# SDcard_eMMC.net
KiCad netlist of a schematic drawn in Altium Designer
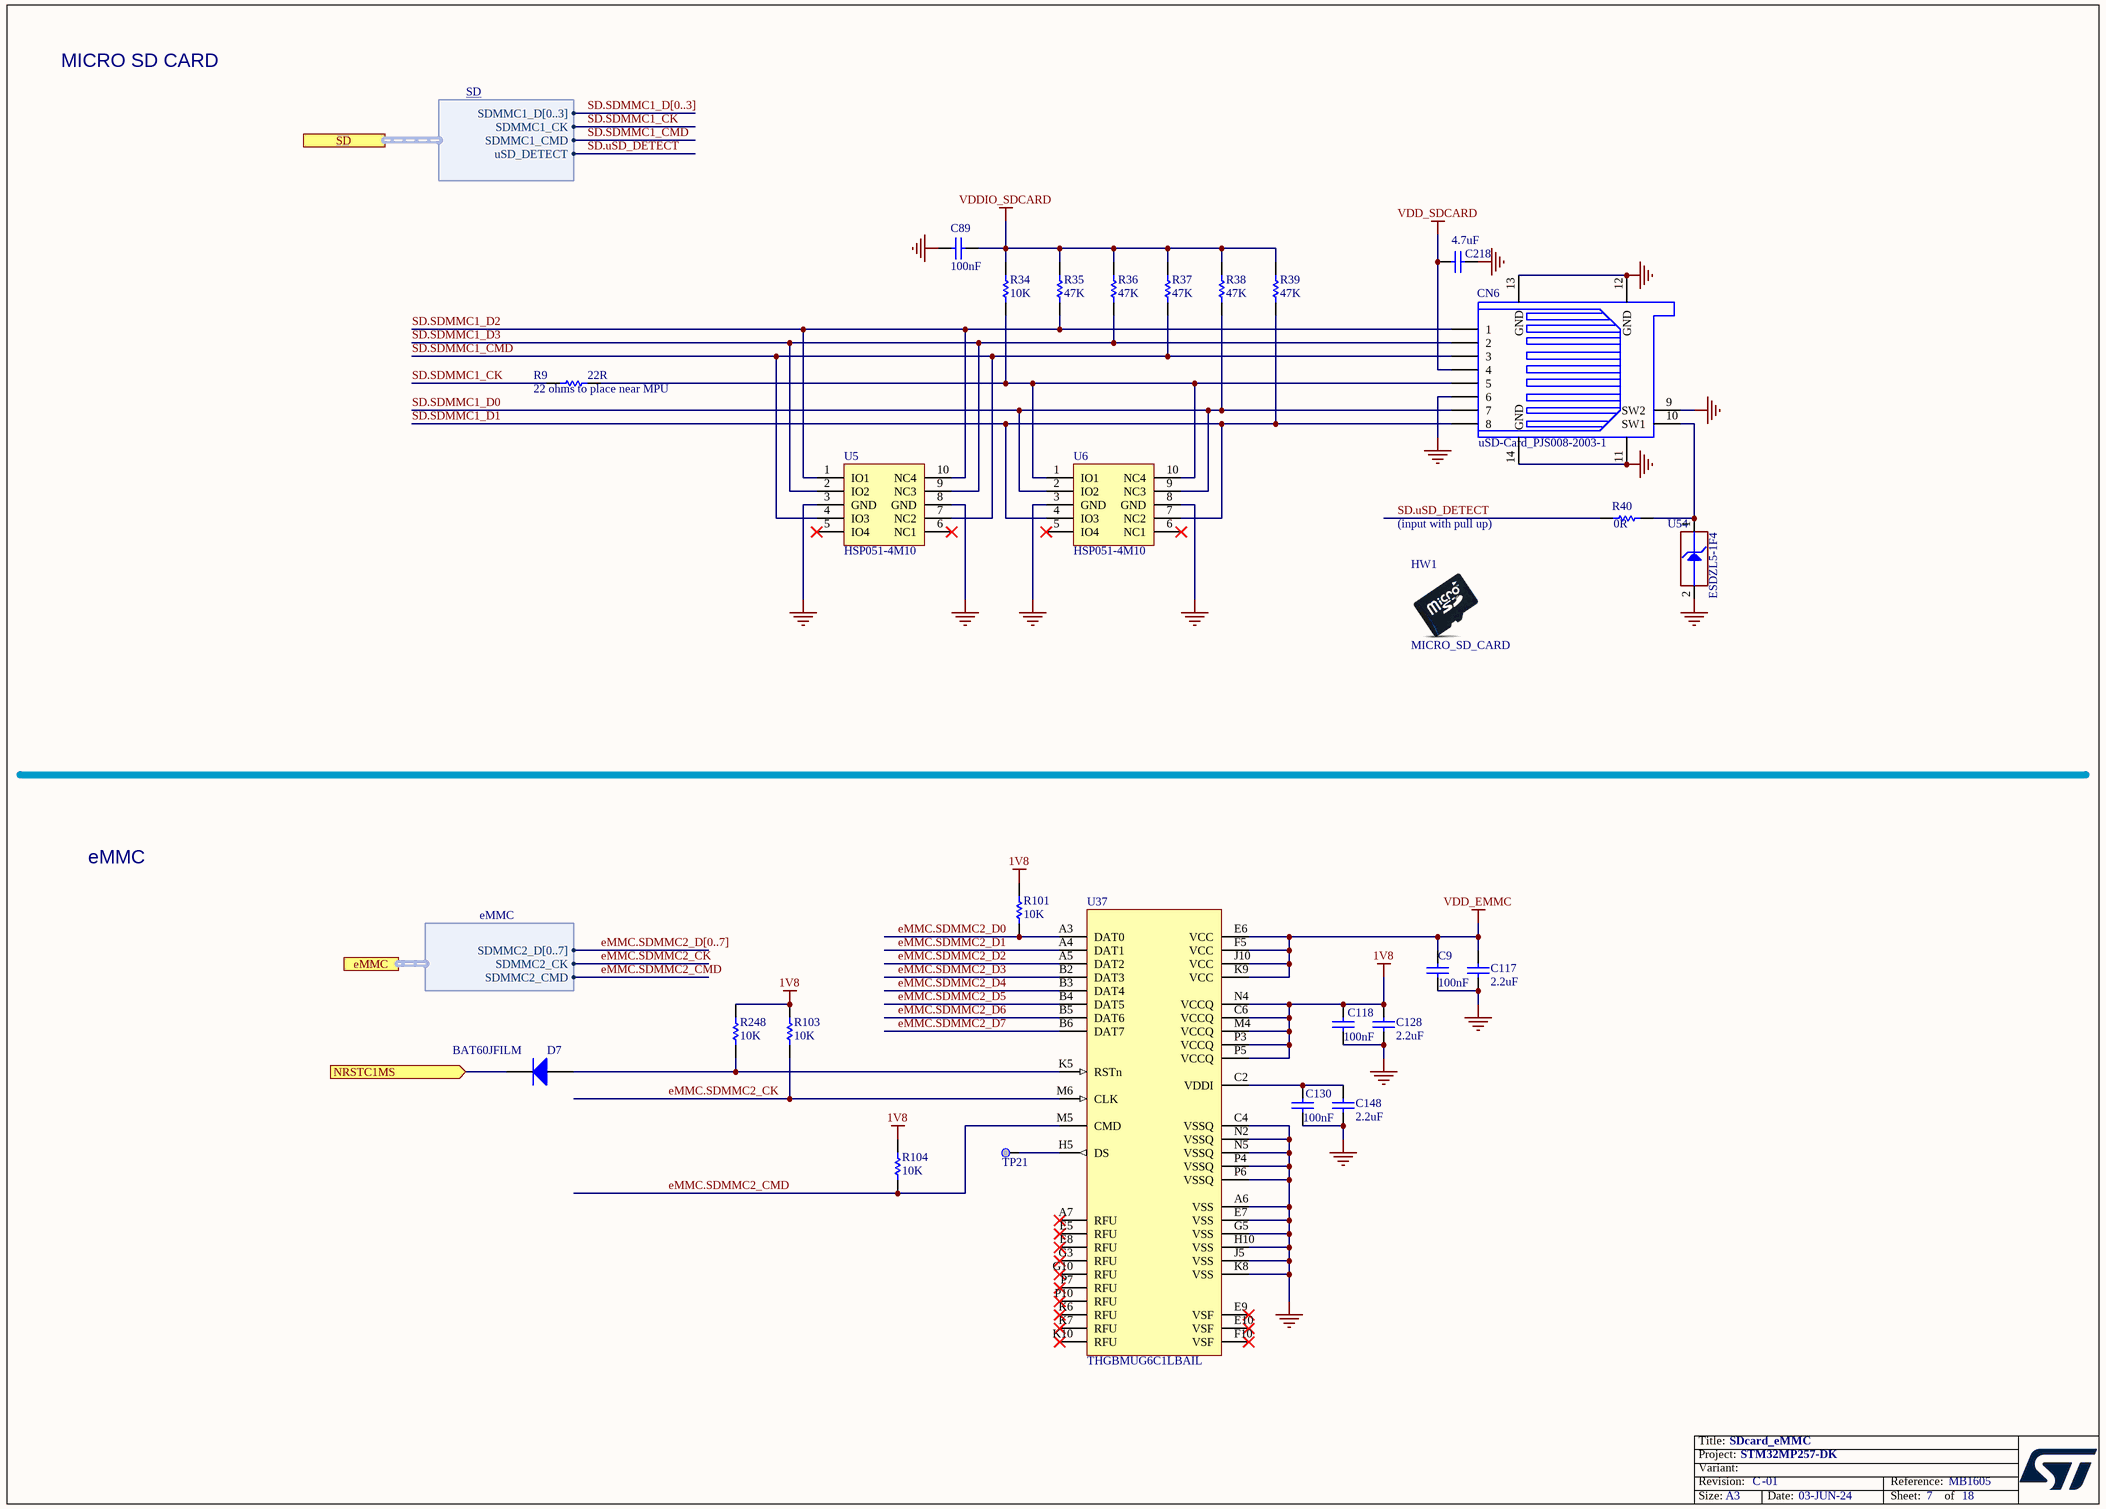
[diagram p0: SDcard_eMMC.SchDoc]

(export (version "E")
  (design (tool "Eeschema 10.0.6"))
  (components
    (comp (ref "C9")
      (value "100nF")
      (footprint "C0402")
      (description "Capacitor, MLCC, 100nF, 16V, X7R, +/-10%, 0402, T=0.5mm")
      (fields (field (name "INTERNAL_PART_NUMBER") "MCD-00006") (field (name "MANUFACTURER") "YAGEO"))
      (libsource (lib "MCD_PARTS_database") (part "Capacitor"))
    )
    (comp (ref "C89")
      (value "100nF")
      (footprint "C0402")
      (description "Capacitor, MLCC, 100nF, 16V, X7R, +/-10%, 0402, T=0.5mm")
      (fields (field (name "INTERNAL_PART_NUMBER") "MCD-00006") (field (name "MANUFACTURER") "YAGEO"))
      (libsource (lib "MCD_PARTS_database") (part "Capacitor"))
    )
    (comp (ref "C117")
      (value "2.2uF")
      (footprint "C0402")
      (description "Capacitor, MLCC, 2.2uF, 6.3V, X5R, +/-10%, 0402, T=0.5mm")
      (fields (field (name "INTERNAL_PART_NUMBER") "MCD-02606") (field (name "MANUFACTURER") "YAGEO"))
      (libsource (lib "MCD_PARTS_database") (part "Capacitor"))
    )
    (comp (ref "C118")
      (value "100nF")
      (footprint "C0402")
      (description "Capacitor, MLCC, 100nF, 16V, X7R, +/-10%, 0402, T=0.5mm")
      (fields (field (name "INTERNAL_PART_NUMBER") "MCD-00006") (field (name "MANUFACTURER") "YAGEO"))
      (libsource (lib "MCD_PARTS_database") (part "Capacitor"))
    )
    (comp (ref "C128")
      (value "2.2uF")
      (footprint "C0402")
      (description "Capacitor, MLCC, 2.2uF, 6.3V, X5R, +/-10%, 0402, T=0.5mm")
      (fields (field (name "INTERNAL_PART_NUMBER") "MCD-02606") (field (name "MANUFACTURER") "YAGEO"))
      (libsource (lib "MCD_PARTS_database") (part "Capacitor"))
    )
    (comp (ref "C130")
      (value "100nF")
      (footprint "C0402")
      (description "Capacitor, MLCC, 100nF, 16V, X7R, +/-10%, 0402, T=0.5mm")
      (fields (field (name "INTERNAL_PART_NUMBER") "MCD-00006") (field (name "MANUFACTURER") "YAGEO"))
      (libsource (lib "MCD_PARTS_database") (part "Capacitor"))
    )
    (comp (ref "C148")
      (value "2.2uF")
      (footprint "C0402")
      (description "Capacitor, MLCC, 2.2uF, 6.3V, X5R, +/-10%, 0402, T=0.5mm")
      (fields (field (name "INTERNAL_PART_NUMBER") "MCD-02606") (field (name "MANUFACTURER") "YAGEO"))
      (libsource (lib "MCD_PARTS_database") (part "Capacitor"))
    )
    (comp (ref "C218")
      (value "4.7uF")
      (footprint "C0402")
      (description "Capacitor, MLCC, 4.7uF, 6V3, X5R, 20%, 0402, T=0,5mm")
      (fields
        (field (name "INTERNAL_PART_NUMBER") "MCD-01356")
        (field (name "MANUFACTURER_PART_NUMBER") "GRM155R60J475ME47")
        (field (name "PROVIDED_BY") "SUBCO")
      )
      (libsource (lib "MCD_PARTS_database") (part "Capacitor"))
    )
    (comp (ref "CN6")
      (value "uSD-Card_PJS008-2003-1")
      (footprint "CON_MICROSD_YAMAICHI_PJS008-2003-1")
      (description "MicroSD Card Conn, Reversed-Type, Mnt Push-Push, Positionning holes")
      (fields
        (field (name "INTERNAL_PART_NUMBER") "MCD-00023")
        (field (name "MANUFACTURER_PART_NUMBER") "PJS008-2003-1")
        (field (name "PROVIDED_BY") "SUBCO")
      )
      (libsource (lib "MCD_PARTS_database") (part "microSD-PJS008-2003"))
    )
    (comp (ref "D7")
      (value "BAT60JFILM")
      (footprint "DIO_SOD323")
      (fields
        (field (name "INTERNAL_PART_NUMBER") "MCD-00034")
        (field (name "BMS_PART_NUMBER") "9151097")
        (field (name "MANUFACTURER") "STMICROELECTRONICS")
      )
      (libsource (lib "MCD_PARTS_database") (part "BAT60JFILM"))
    )
    (comp (ref "HW1")
      (value "MICRO_SD_CARD")
      (description "MICRO_SD_CARD, SANDISK, 16GB, Class10, 3V")
      (fields (field (name "INTERNAL_PART_NUMBER") "MCD-03307") (field (name "MANUFACTURER") "SANDISK"))
      (libsource (lib "MCD_PARTS_database") (part "Micro_SD_card"))
    )
    (comp (ref "R9")
      (value "22R")
      (footprint "R0201_H0P23")
      (description "Resistor, 22R, 0201, +/-1%, 1/20W")
      (fields
        (field (name "INTERNAL_PART_NUMBER") "MCD-02978")
        (field (name "MANUFACTURER_PART_NUMBER") "RC0201FR-0722RL")
      )
      (libsource (lib "MCD_PARTS_database") (part "Resistor"))
    )
    (comp (ref "R34")
      (value "10K")
      (footprint "R0402")
      (description "Resistor,10K,0402,1%,1/16W")
      (fields
        (field (name "INTERNAL_PART_NUMBER") "MCD-00053")
        (field (name "MANUFACTURER_PART_NUMBER") "RC0402FR-0710KL")
        (field (name "PROVIDED_BY") "SUBCO")
      )
      (libsource (lib "MCD_PARTS_database") (part "Resistor"))
    )
    (comp (ref "R35")
      (value "47K")
      (footprint "R0402")
      (description "Resistor,47K,0402,1%,1/16W")
      (fields
        (field (name "INTERNAL_PART_NUMBER") "MCD-00063")
        (field (name "MANUFACTURER_PART_NUMBER") "RC0402FR-0747KL")
        (field (name "PROVIDED_BY") "SUBCO")
      )
      (libsource (lib "MCD_PARTS_database") (part "Resistor"))
    )
    (comp (ref "R36")
      (value "47K")
      (footprint "R0402")
      (description "Resistor,47K,0402,1%,1/16W")
      (fields
        (field (name "INTERNAL_PART_NUMBER") "MCD-00063")
        (field (name "MANUFACTURER_PART_NUMBER") "RC0402FR-0747KL")
        (field (name "PROVIDED_BY") "SUBCO")
      )
      (libsource (lib "MCD_PARTS_database") (part "Resistor"))
    )
    (comp (ref "R37")
      (value "47K")
      (footprint "R0402")
      (description "Resistor,47K,0402,1%,1/16W")
      (fields
        (field (name "INTERNAL_PART_NUMBER") "MCD-00063")
        (field (name "MANUFACTURER_PART_NUMBER") "RC0402FR-0747KL")
        (field (name "PROVIDED_BY") "SUBCO")
      )
      (libsource (lib "MCD_PARTS_database") (part "Resistor"))
    )
    (comp (ref "R38")
      (value "47K")
      (footprint "R0402")
      (description "Resistor,47K,0402,1%,1/16W")
      (fields
        (field (name "INTERNAL_PART_NUMBER") "MCD-00063")
        (field (name "MANUFACTURER_PART_NUMBER") "RC0402FR-0747KL")
        (field (name "PROVIDED_BY") "SUBCO")
      )
      (libsource (lib "MCD_PARTS_database") (part "Resistor"))
    )
    (comp (ref "R39")
      (value "47K")
      (footprint "R0402")
      (description "Resistor,47K,0402,1%,1/16W")
      (fields
        (field (name "INTERNAL_PART_NUMBER") "MCD-00063")
        (field (name "MANUFACTURER_PART_NUMBER") "RC0402FR-0747KL")
        (field (name "PROVIDED_BY") "SUBCO")
      )
      (libsource (lib "MCD_PARTS_database") (part "Resistor"))
    )
    (comp (ref "R40")
      (value "0R")
      (footprint "R0402")
      (description "Resistor,0R,0402,5%,1/16W")
      (fields
        (field (name "INTERNAL_PART_NUMBER") "MCD-00052")
        (field (name "MANUFACTURER_PART_NUMBER") "RC0402JR-070RL")
        (field (name "PROVIDED_BY") "SUBCO")
      )
      (libsource (lib "MCD_PARTS_database") (part "Resistor"))
    )
    (comp (ref "R101")
      (value "10K")
      (footprint "R0402")
      (description "Resistor,10K,0402,1%,1/16W")
      (fields
        (field (name "INTERNAL_PART_NUMBER") "MCD-00053")
        (field (name "MANUFACTURER_PART_NUMBER") "RC0402FR-0710KL")
        (field (name "PROVIDED_BY") "SUBCO")
      )
      (libsource (lib "MCD_PARTS_database") (part "Resistor"))
    )
    (comp (ref "R103")
      (value "10K")
      (footprint "R0402")
      (description "Resistor,10K,0402,1%,1/16W")
      (fields
        (field (name "INTERNAL_PART_NUMBER") "MCD-00053")
        (field (name "MANUFACTURER_PART_NUMBER") "RC0402FR-0710KL")
        (field (name "PROVIDED_BY") "SUBCO")
      )
      (libsource (lib "MCD_PARTS_database") (part "Resistor"))
    )
    (comp (ref "R104")
      (value "10K")
      (footprint "R0402")
      (description "Resistor,10K,0402,1%,1/16W")
      (fields
        (field (name "INTERNAL_PART_NUMBER") "MCD-00053")
        (field (name "MANUFACTURER_PART_NUMBER") "RC0402FR-0710KL")
        (field (name "PROVIDED_BY") "SUBCO")
      )
      (libsource (lib "MCD_PARTS_database") (part "Resistor"))
    )
    (comp (ref "R248")
      (value "10K")
      (footprint "R0402")
      (description "Resistor,10K,0402,1%,1/16W")
      (fields
        (field (name "INTERNAL_PART_NUMBER") "MCD-00053")
        (field (name "MANUFACTURER_PART_NUMBER") "RC0402FR-0710KL")
        (field (name "PROVIDED_BY") "SUBCO")
      )
      (libsource (lib "MCD_PARTS_database") (part "Resistor"))
    )
    (comp (ref "TP21")
      (value "Test Point")
      (footprint "TP_SMD_1MM")
      (description "Test Point 1mm")
      (fields
        (field (name "INTERNAL_PART_NUMBER") "MCD-00074")
        (field (name "MANUFACTURER_PART_NUMBER") "n/a")
      )
      (libsource (lib "MCD_PARTS_database") (part "Test Point"))
    )
    (comp (ref "U5")
      (value "HSP051-4M10")
      (footprint "ESD_UQFN-10L_2P5X1_P050")
      (description "4-line ESD protection for high speed lines")
      (fields
        (field (name "INTERNAL_PART_NUMBER") "MCD-00667")
        (field (name "MANUFACTURER") "STMICROELECTRONICS")
        (field (name "PROVIDED_BY") "SUBCO with ST control")
      )
      (libsource (lib "MCD_PARTS_database") (part "HSP051-4M10"))
    )
    (comp (ref "U6")
      (value "HSP051-4M10")
      (footprint "ESD_UQFN-10L_2P5X1_P050")
      (description "4-line ESD protection for high speed lines")
      (fields
        (field (name "INTERNAL_PART_NUMBER") "MCD-00667")
        (field (name "MANUFACTURER") "STMICROELECTRONICS")
        (field (name "PROVIDED_BY") "SUBCO with ST control")
      )
      (libsource (lib "MCD_PARTS_database") (part "HSP051-4M10"))
    )
    (comp (ref "U37")
      (value "THGBMUG6C1LBAIL")
      (footprint "ICC_WFBGA153_13X11P5_P050")
      (description "Memory, eMMC, 3V3, 8Gbit, 52MHz , V5.1")
      (fields (field (name "INTERNAL_PART_NUMBER") "MCD-04155") (field (name "MANUFACTURER") "KIOXIA"))
      (libsource (lib "MCD_PARTS_database") (part "eMMC_THGBMUG6C1LBAIL"))
    )
    (comp (ref "U54")
      (value "ESDZL5-1F4")
      (footprint "ESD_ST0201")
      (description "ESD protection , 0201")
      (fields
        (field (name "INTERNAL_PART_NUMBER") "MCD-03501")
        (field (name "MANUFACTURER") "STMICROELECTRONICS")
      )
      (libsource (lib "MCD_PARTS_database") (part "ESD-TRANSIL"))
    )
  )
  (nets
    (net (code "3") (name "/NRSTC1MS") (class "Default")
      (node (ref "D7") (pin "2") (pinfunction "K_2") (pintype "passive"))
    )
    (net (code "4") (name "/SD.SDMMC1_CK") (class "Default")
      (node (ref "R9") (pin "1") (pinfunction "1_1") (pintype "passive"))
    )
    (net (code "5") (name "/SD.SDMMC1_CMD") (class "Default")
      (node (ref "CN6") (pin "3") (pinfunction "3_3") (pintype "passive"))
      (node (ref "R37") (pin "1") (pinfunction "1_1") (pintype "passive"))
      (node (ref "U5") (pin "4") (pinfunction "IO3_4") (pintype "passive"))
      (node (ref "U5") (pin "7") (pinfunction "NC2_7") (pintype "passive"))
    )
    (net (code "6") (name "/SD.SDMMC1_D0") (class "Default")
      (node (ref "CN6") (pin "7") (pinfunction "7_7") (pintype "passive"))
      (node (ref "R38") (pin "1") (pinfunction "1_1") (pintype "passive"))
      (node (ref "U6") (pin "2") (pinfunction "IO2_2") (pintype "passive"))
      (node (ref "U6") (pin "9") (pinfunction "NC3_9") (pintype "passive"))
    )
    (net (code "7") (name "/SD.SDMMC1_D1") (class "Default")
      (node (ref "CN6") (pin "8") (pinfunction "8_8") (pintype "passive"))
      (node (ref "R39") (pin "1") (pinfunction "1_1") (pintype "passive"))
      (node (ref "U6") (pin "4") (pinfunction "IO3_4") (pintype "passive"))
      (node (ref "U6") (pin "7") (pinfunction "NC2_7") (pintype "passive"))
    )
    (net (code "8") (name "/SD.SDMMC1_D2") (class "Default")
      (node (ref "CN6") (pin "1") (pinfunction "1_1") (pintype "passive"))
      (node (ref "R35") (pin "1") (pinfunction "1_1") (pintype "passive"))
      (node (ref "U5") (pin "1") (pinfunction "IO1_1") (pintype "passive"))
      (node (ref "U5") (pin "10") (pinfunction "NC4_10") (pintype "passive"))
    )
    (net (code "9") (name "/SD.SDMMC1_D3") (class "Default")
      (node (ref "CN6") (pin "2") (pinfunction "2_2") (pintype "passive"))
      (node (ref "R36") (pin "1") (pinfunction "1_1") (pintype "passive"))
      (node (ref "U5") (pin "2") (pinfunction "IO2_2") (pintype "passive"))
      (node (ref "U5") (pin "9") (pinfunction "NC3_9") (pintype "passive"))
    )
    (net (code "11") (name "/SD.uSD_DETECT") (class "Default")
      (node (ref "R40") (pin "1") (pinfunction "1_1") (pintype "passive"))
    )
    (net (code "12") (name "/eMMC.SDMMC2_CK") (class "Default")
      (node (ref "R103") (pin "1") (pinfunction "1_1") (pintype "passive"))
      (node (ref "U37") (pin "M6") (pinfunction "CLK_M6") (pintype "input"))
    )
    (net (code "13") (name "/eMMC.SDMMC2_CMD") (class "Default")
      (node (ref "R104") (pin "1") (pinfunction "1_1") (pintype "passive"))
      (node (ref "U37") (pin "M5") (pinfunction "CMD_M5") (pintype "passive"))
    )
    (net (code "14") (name "/eMMC.SDMMC2_D0") (class "Default")
      (node (ref "R101") (pin "1") (pinfunction "1_1") (pintype "passive"))
      (node (ref "U37") (pin "A3") (pinfunction "DAT0_A3") (pintype "passive"))
    )
    (net (code "15") (name "/eMMC.SDMMC2_D1") (class "Default")
      (node (ref "U37") (pin "A4") (pinfunction "DAT1_A4") (pintype "passive"))
    )
    (net (code "16") (name "/eMMC.SDMMC2_D2") (class "Default")
      (node (ref "U37") (pin "A5") (pinfunction "DAT2_A5") (pintype "passive"))
    )
    (net (code "17") (name "/eMMC.SDMMC2_D3") (class "Default")
      (node (ref "U37") (pin "B2") (pinfunction "DAT3_B2") (pintype "passive"))
    )
    (net (code "18") (name "/eMMC.SDMMC2_D4") (class "Default")
      (node (ref "U37") (pin "B3") (pinfunction "DAT4_B3") (pintype "passive"))
    )
    (net (code "19") (name "/eMMC.SDMMC2_D5") (class "Default")
      (node (ref "U37") (pin "B4") (pinfunction "DAT5_B4") (pintype "passive"))
    )
    (net (code "20") (name "/eMMC.SDMMC2_D6") (class "Default")
      (node (ref "U37") (pin "B5") (pinfunction "DAT6_B5") (pintype "passive"))
    )
    (net (code "21") (name "/eMMC.SDMMC2_D7") (class "Default")
      (node (ref "U37") (pin "B6") (pinfunction "DAT7_B6") (pintype "passive"))
    )
    (net (code "25") (name "1V8") (class "Default")
      (node (ref "C118") (pin "2") (pinfunction "2_2") (pintype "passive"))
      (node (ref "C128") (pin "2") (pinfunction "2_2") (pintype "passive"))
      (node (ref "R101") (pin "2") (pinfunction "2_2") (pintype "passive"))
      (node (ref "R103") (pin "2") (pinfunction "2_2") (pintype "passive"))
      (node (ref "R104") (pin "2") (pinfunction "2_2") (pintype "passive"))
      (node (ref "R248") (pin "2") (pinfunction "2_2") (pintype "passive"))
      (node (ref "U37") (pin "C6") (pinfunction "VCCQ_C6") (pintype "passive"))
      (node (ref "U37") (pin "M4") (pinfunction "VCCQ_M4") (pintype "passive"))
      (node (ref "U37") (pin "N4") (pinfunction "VCCQ_N4") (pintype "passive"))
      (node (ref "U37") (pin "P3") (pinfunction "VCCQ_P3") (pintype "passive"))
      (node (ref "U37") (pin "P5") (pinfunction "VCCQ_P5") (pintype "passive"))
    )
    (net (code "26") (name "GND") (class "Default")
      (node (ref "C117") (pin "1") (pinfunction "1_1") (pintype "passive"))
      (node (ref "C118") (pin "1") (pinfunction "1_1") (pintype "passive"))
      (node (ref "C128") (pin "1") (pinfunction "1_1") (pintype "passive"))
      (node (ref "C130") (pin "1") (pinfunction "1_1") (pintype "passive"))
      (node (ref "C148") (pin "1") (pinfunction "1_1") (pintype "passive"))
      (node (ref "C218") (pin "1") (pinfunction "1_1") (pintype "passive"))
      (node (ref "C89") (pin "1") (pinfunction "1_1") (pintype "passive"))
      (node (ref "C9") (pin "1") (pinfunction "1_1") (pintype "passive"))
      (node (ref "CN6") (pin "11") (pinfunction "GND_11") (pintype "passive"))
      (node (ref "CN6") (pin "12") (pinfunction "GND_12") (pintype "passive"))
      (node (ref "CN6") (pin "13") (pinfunction "GND_13") (pintype "passive"))
      (node (ref "CN6") (pin "14") (pinfunction "GND_14") (pintype "passive"))
      (node (ref "CN6") (pin "6") (pinfunction "6_6") (pintype "passive"))
      (node (ref "CN6") (pin "9") (pinfunction "SW2_9") (pintype "passive"))
      (node (ref "U37") (pin "A6") (pinfunction "VSS_A6") (pintype "passive"))
      (node (ref "U37") (pin "C4") (pinfunction "VSSQ_C4") (pintype "passive"))
      (node (ref "U37") (pin "E7") (pinfunction "VSS_E7") (pintype "passive"))
      (node (ref "U37") (pin "G5") (pinfunction "VSS_G5") (pintype "passive"))
      (node (ref "U37") (pin "H10") (pinfunction "VSS_H10") (pintype "passive"))
      (node (ref "U37") (pin "J5") (pinfunction "VSS_J5") (pintype "passive"))
      (node (ref "U37") (pin "K8") (pinfunction "VSS_K8") (pintype "passive"))
      (node (ref "U37") (pin "N2") (pinfunction "VSSQ_N2") (pintype "passive"))
      (node (ref "U37") (pin "N5") (pinfunction "VSSQ_N5") (pintype "passive"))
      (node (ref "U37") (pin "P4") (pinfunction "VSSQ_P4") (pintype "passive"))
      (node (ref "U37") (pin "P6") (pinfunction "VSSQ_P6") (pintype "passive"))
      (node (ref "U5") (pin "3") (pinfunction "GND_3") (pintype "passive"))
      (node (ref "U5") (pin "8") (pinfunction "GND_8") (pintype "passive"))
      (node (ref "U54") (pin "2") (pinfunction "GND_2") (pintype "passive"))
      (node (ref "U6") (pin "3") (pinfunction "GND_3") (pintype "passive"))
      (node (ref "U6") (pin "8") (pinfunction "GND_8") (pintype "passive"))
    )
    (net (code "27") (name "Net-(CN6-SW1)") (class "Default")
      (node (ref "CN6") (pin "10") (pinfunction "SW1_10") (pintype "passive"))
      (node (ref "R40") (pin "2") (pinfunction "2_2") (pintype "passive"))
      (node (ref "U54") (pin "1") (pinfunction "IO1_1") (pintype "passive"))
    )
    (net (code "28") (name "Net-(D7-A)") (class "Default")
      (node (ref "D7") (pin "1") (pinfunction "A_1") (pintype "passive"))
      (node (ref "R248") (pin "1") (pinfunction "1_1") (pintype "passive"))
      (node (ref "U37") (pin "K5") (pinfunction "RSTn_K5") (pintype "input"))
    )
    (net (code "29") (name "Net-(U6-IO1)") (class "Default")
      (node (ref "CN6") (pin "5") (pinfunction "5_5") (pintype "passive"))
      (node (ref "R34") (pin "1") (pinfunction "1_1") (pintype "passive"))
      (node (ref "R9") (pin "2") (pinfunction "2_2") (pintype "passive"))
      (node (ref "U6") (pin "1") (pinfunction "IO1_1") (pintype "passive"))
      (node (ref "U6") (pin "10") (pinfunction "NC4_10") (pintype "passive"))
    )
    (net (code "30") (name "Net-(U37-DS)") (class "Default")
      (node (ref "TP21") (pin "1") (pinfunction "1_1") (pintype "passive"))
      (node (ref "U37") (pin "H5") (pinfunction "DS_H5") (pintype "output"))
    )
    (net (code "31") (name "Net-(U37-VDDI)") (class "Default")
      (node (ref "C130") (pin "2") (pinfunction "2_2") (pintype "passive"))
      (node (ref "C148") (pin "2") (pinfunction "2_2") (pintype "passive"))
      (node (ref "U37") (pin "C2") (pinfunction "VDDI_C2") (pintype "passive"))
    )
    (net (code "32") (name "VDDIO_SDCARD") (class "Default")
      (node (ref "C89") (pin "2") (pinfunction "2_2") (pintype "passive"))
      (node (ref "R34") (pin "2") (pinfunction "2_2") (pintype "passive"))
      (node (ref "R35") (pin "2") (pinfunction "2_2") (pintype "passive"))
      (node (ref "R36") (pin "2") (pinfunction "2_2") (pintype "passive"))
      (node (ref "R37") (pin "2") (pinfunction "2_2") (pintype "passive"))
      (node (ref "R38") (pin "2") (pinfunction "2_2") (pintype "passive"))
      (node (ref "R39") (pin "2") (pinfunction "2_2") (pintype "passive"))
    )
    (net (code "33") (name "VDD_EMMC") (class "Default")
      (node (ref "C117") (pin "2") (pinfunction "2_2") (pintype "passive"))
      (node (ref "C9") (pin "2") (pinfunction "2_2") (pintype "passive"))
      (node (ref "U37") (pin "E6") (pinfunction "VCC_E6") (pintype "passive"))
      (node (ref "U37") (pin "F5") (pinfunction "VCC_F5") (pintype "passive"))
      (node (ref "U37") (pin "J10") (pinfunction "VCC_J10") (pintype "passive"))
      (node (ref "U37") (pin "K9") (pinfunction "VCC_K9") (pintype "passive"))
    )
    (net (code "34") (name "VDD_SDCARD") (class "Default")
      (node (ref "C218") (pin "2") (pinfunction "2_2") (pintype "passive"))
      (node (ref "CN6") (pin "4") (pinfunction "4_4") (pintype "passive"))
    )
    (net (code "35") (name "unconnected-(U5-IO4-Pad5)") (class "Default")
      (node (ref "U5") (pin "5") (pinfunction "IO4_5") (pintype "passive+no_connect"))
    )
    (net (code "36") (name "unconnected-(U5-NC1-Pad6)") (class "Default")
      (node (ref "U5") (pin "6") (pinfunction "NC1_6") (pintype "passive+no_connect"))
    )
    (net (code "37") (name "unconnected-(U6-IO4-Pad5)") (class "Default")
      (node (ref "U6") (pin "5") (pinfunction "IO4_5") (pintype "passive+no_connect"))
    )
    (net (code "38") (name "unconnected-(U6-NC1-Pad6)") (class "Default")
      (node (ref "U6") (pin "6") (pinfunction "NC1_6") (pintype "passive+no_connect"))
    )
    (net (code "39") (name "unconnected-(U37-RFU-PadA7)") (class "Default")
      (node (ref "U37") (pin "A7") (pinfunction "RFU_A7") (pintype "passive+no_connect"))
    )
    (net (code "40") (name "unconnected-(U37-RFU-PadE5)") (class "Default")
      (node (ref "U37") (pin "E5") (pinfunction "RFU_E5") (pintype "passive+no_connect"))
    )
    (net (code "41") (name "unconnected-(U37-RFU-PadE8)") (class "Default")
      (node (ref "U37") (pin "E8") (pinfunction "RFU_E8") (pintype "passive+no_connect"))
    )
    (net (code "42") (name "unconnected-(U37-RFU-PadG3)") (class "Default")
      (node (ref "U37") (pin "G3") (pinfunction "RFU_G3") (pintype "passive+no_connect"))
    )
    (net (code "43") (name "unconnected-(U37-RFU-PadG10)") (class "Default")
      (node (ref "U37") (pin "G10") (pinfunction "RFU_G10") (pintype "passive+no_connect"))
    )
    (net (code "44") (name "unconnected-(U37-RFU-PadK6)") (class "Default")
      (node (ref "U37") (pin "K6") (pinfunction "RFU_K6") (pintype "passive+no_connect"))
    )
    (net (code "45") (name "unconnected-(U37-RFU-PadK7)") (class "Default")
      (node (ref "U37") (pin "K7") (pinfunction "RFU_K7") (pintype "passive+no_connect"))
    )
    (net (code "46") (name "unconnected-(U37-RFU-PadK10)") (class "Default")
      (node (ref "U37") (pin "K10") (pinfunction "RFU_K10") (pintype "passive+no_connect"))
    )
    (net (code "47") (name "unconnected-(U37-RFU-PadP7)") (class "Default")
      (node (ref "U37") (pin "P7") (pinfunction "RFU_P7") (pintype "passive+no_connect"))
    )
    (net (code "48") (name "unconnected-(U37-RFU-PadP10)") (class "Default")
      (node (ref "U37") (pin "P10") (pinfunction "RFU_P10") (pintype "passive+no_connect"))
    )
    (net (code "49") (name "unconnected-(U37-VSF-PadE9)") (class "Default")
      (node (ref "U37") (pin "E9") (pinfunction "VSF_E9") (pintype "passive+no_connect"))
    )
    (net (code "50") (name "unconnected-(U37-VSF-PadE10)") (class "Default")
      (node (ref "U37") (pin "E10") (pinfunction "VSF_E10") (pintype "passive+no_connect"))
    )
    (net (code "51") (name "unconnected-(U37-VSF-PadF10)") (class "Default")
      (node (ref "U37") (pin "F10") (pinfunction "VSF_F10") (pintype "passive+no_connect"))
    )
  )
)
